# GPS_breakout-v10.net
KiCad netlist of a schematic drawn in EAGLE
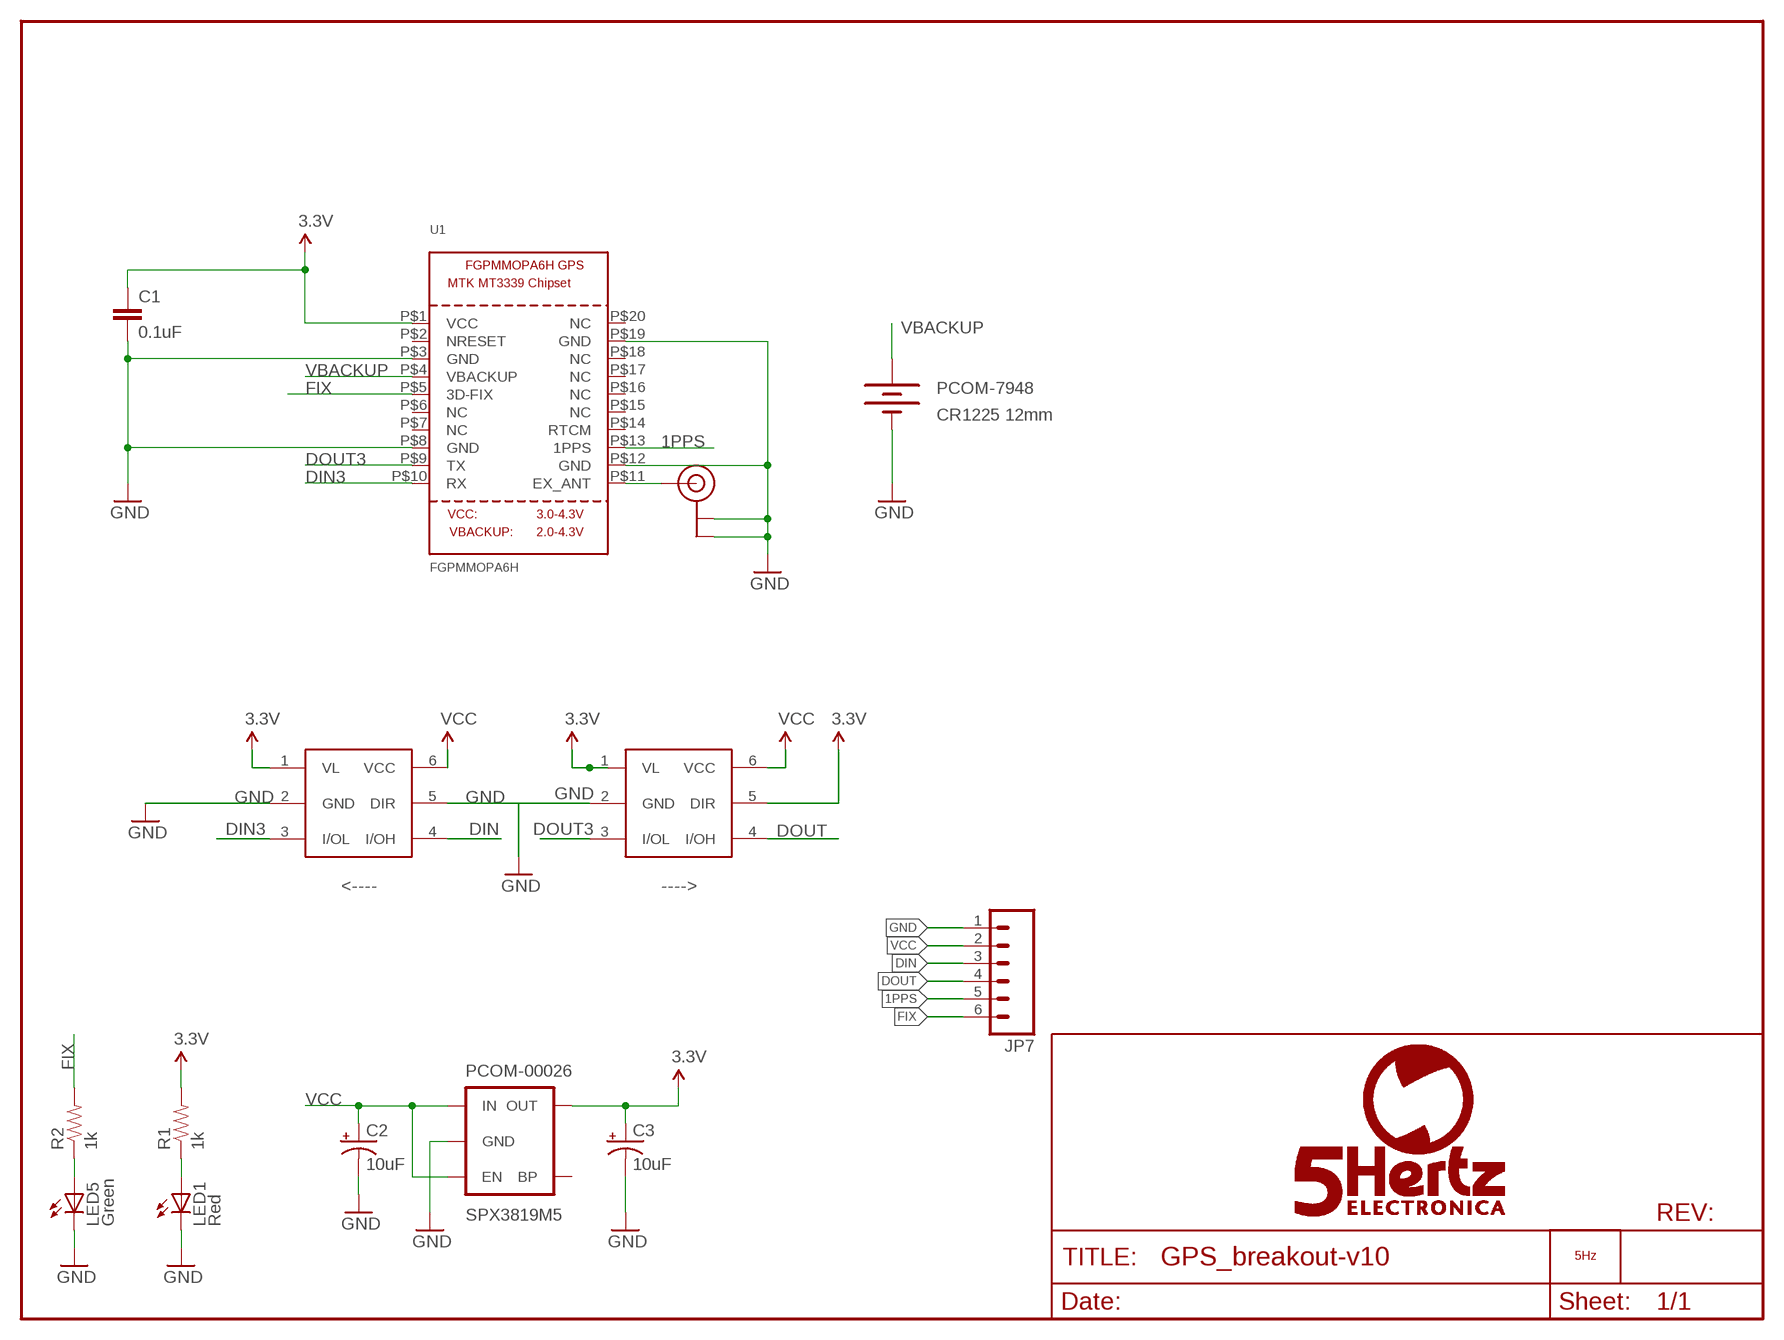
[diagram p0: schematic, sheet 1]

(export (version "E")
  (design (tool "Eeschema 10.0.6"))
  (components
    (comp (ref "C1")
      (value "0.1uF")
      (footprint "eagle-import:0603-CAP")
      (libsource (lib "eagle-import") (part "CAP0603-CAP"))
    )
    (comp (ref "C2")
      (value "10uF")
      (footprint "eagle-import:EIA3216")
      (libsource (lib "eagle-import") (part "CAP_POL1206"))
    )
    (comp (ref "C3")
      (value "10uF")
      (footprint "eagle-import:EIA3216")
      (libsource (lib "eagle-import") (part "CAP_POL1206"))
    )
    (comp (ref "JP7")
      (value "M06SIP")
      (footprint "eagle-import:1X06")
      (libsource (lib "eagle-import") (part "M06SIP"))
    )
    (comp (ref "LED1")
      (value "Red")
      (footprint "eagle-import:LED-0603")
      (libsource (lib "eagle-import") (part "LED0603"))
    )
    (comp (ref "LED5")
      (value "Green")
      (footprint "eagle-import:LED-0603")
      (libsource (lib "eagle-import") (part "LED0603"))
    )
    (comp (ref "LOGO1")
      (value "LOGO_5HZ_MAIN_15MM")
      (footprint "eagle-import:5HZ_LOGO_MAIN_15MM")
      (libsource (lib "eagle-import") (part "LOGO_5HZ_MAIN_15MM"))
    )
    (comp (ref "PCOM-00026")
      (value "SPX3819M5")
      (footprint "eagle-import:SOT23-5")
      (libsource (lib "eagle-import") (part "V_REG_LDOSMD"))
    )
    (comp (ref "PCOM-7948")
      (value "CR1225 12mm")
      (footprint "eagle-import:BATTCON_12MM_PTH")
      (libsource (lib "eagle-import") (part "BATTERY12PTH"))
    )
    (comp (ref "R1")
      (value "1k")
      (footprint "eagle-import:0603-RES")
      (libsource (lib "eagle-import") (part "RESISTOR0603-RES"))
    )
    (comp (ref "R2")
      (value "1k")
      (footprint "eagle-import:0603-RES")
      (libsource (lib "eagle-import") (part "RESISTOR0603-RES"))
    )
    (comp (ref "U$7")
      (value "MAX337")
      (footprint "eagle-import:SOT-363")
      (libsource (lib "eagle-import") (part "MAX337"))
    )
    (comp (ref "U$8")
      (value "MAX337")
      (footprint "eagle-import:SOT-363")
      (libsource (lib "eagle-import") (part "MAX337"))
    )
    (comp (ref "U$20")
      (value "U.FL")
      (footprint "eagle-import:U.FL")
      (libsource (lib "eagle-import") (part "U.FL"))
    )
    (comp (ref "U1")
      (value "FGPMMOPA6H")
      (footprint "eagle-import:FGPMMOPA6H")
      (libsource (lib "eagle-import") (part "GPS_FGPMMOPA6H"))
    )
  )
  (nets
    (net (code "1") (name "/DIN3") (class "Default")
      (node (ref "U$7") (pin "3") (pinfunction "I/OL_3") (pintype "bidirectional"))
      (node (ref "U1") (pin "P$10") (pinfunction "RX_P$10") (pintype "bidirectional"))
    )
    (net (code "2") (name "/DOUT3") (class "Default")
      (node (ref "U$8") (pin "3") (pinfunction "I/OL_3") (pintype "bidirectional"))
      (node (ref "U1") (pin "P$9") (pinfunction "TX_P$9") (pintype "bidirectional"))
    )
    (net (code "3") (name "/VBACKUP") (class "Default")
      (node (ref "PCOM-7948") (pin "VCC@1") (pinfunction "+_VCC@1") (pintype "power_in"))
      (node (ref "U1") (pin "P$4") (pinfunction "VBACKUP_P$4") (pintype "bidirectional"))
    )
    (net (code "4") (name "1PPS") (class "Default")
      (node (ref "JP7") (pin "5") (pinfunction "5_5") (pintype "passive"))
      (node (ref "U1") (pin "P$13") (pinfunction "1PPS_P$13") (pintype "bidirectional"))
    )
    (net (code "5") (name "3.3V") (class "Default")
      (node (ref "C1") (pin "1") (pinfunction "1_1") (pintype "passive"))
      (node (ref "C3") (pin "A") (pinfunction "+_A") (pintype "passive"))
      (node (ref "PCOM-00026") (pin "5") (pinfunction "OUT_5") (pintype "passive"))
      (node (ref "R1") (pin "2") (pinfunction "2_2") (pintype "passive"))
      (node (ref "U$7") (pin "1") (pinfunction "VL_1") (pintype "bidirectional"))
      (node (ref "U$8") (pin "1") (pinfunction "VL_1") (pintype "bidirectional"))
      (node (ref "U$8") (pin "5") (pinfunction "DIR_5") (pintype "bidirectional"))
      (node (ref "U1") (pin "P$1") (pinfunction "VCC_P$1") (pintype "bidirectional"))
    )
    (net (code "6") (name "DIN") (class "Default")
      (node (ref "JP7") (pin "3") (pinfunction "3_3") (pintype "passive"))
      (node (ref "U$7") (pin "4") (pinfunction "I/OH_4") (pintype "bidirectional"))
    )
    (net (code "7") (name "DOUT") (class "Default")
      (node (ref "JP7") (pin "4") (pinfunction "4_4") (pintype "passive"))
      (node (ref "U$8") (pin "4") (pinfunction "I/OH_4") (pintype "bidirectional"))
    )
    (net (code "8") (name "FIX") (class "Default")
      (node (ref "JP7") (pin "6") (pinfunction "6_6") (pintype "passive"))
      (node (ref "R2") (pin "2") (pinfunction "2_2") (pintype "passive"))
      (node (ref "U1") (pin "P$5") (pinfunction "3D-FIX_P$5") (pintype "bidirectional"))
    )
    (net (code "9") (name "GND") (class "Default")
      (node (ref "C1") (pin "2") (pinfunction "2_2") (pintype "passive"))
      (node (ref "C2") (pin "C") (pinfunction "-_C") (pintype "passive"))
      (node (ref "C3") (pin "C") (pinfunction "-_C") (pintype "passive"))
      (node (ref "JP7") (pin "1") (pinfunction "1_1") (pintype "passive"))
      (node (ref "LED1") (pin "C") (pinfunction "C_C") (pintype "passive"))
      (node (ref "LED5") (pin "C") (pinfunction "C_C") (pintype "passive"))
      (node (ref "PCOM-00026") (pin "2") (pinfunction "GND_2") (pintype "input"))
      (node (ref "PCOM-7948") (pin "GND") (pinfunction "-_GND") (pintype "power_in"))
      (node (ref "U$20") (pin "P$1") (pinfunction "GND_P$1") (pintype "bidirectional"))
      (node (ref "U$20") (pin "P$2") (pinfunction "GND_P$2") (pintype "bidirectional"))
      (node (ref "U$7") (pin "2") (pinfunction "GND_2") (pintype "bidirectional"))
      (node (ref "U$7") (pin "5") (pinfunction "DIR_5") (pintype "bidirectional"))
      (node (ref "U$8") (pin "2") (pinfunction "GND_2") (pintype "bidirectional"))
      (node (ref "U1") (pin "P$12") (pinfunction "GND_P$12") (pintype "bidirectional"))
      (node (ref "U1") (pin "P$19") (pinfunction "GND_P$19") (pintype "bidirectional"))
      (node (ref "U1") (pin "P$3") (pinfunction "GND_P$3") (pintype "bidirectional"))
      (node (ref "U1") (pin "P$8") (pinfunction "GND_P$8") (pintype "bidirectional"))
    )
    (net (code "10") (name "Net-(LED1-PadA)") (class "Default")
      (node (ref "LED1") (pin "A") (pinfunction "A_A") (pintype "passive"))
      (node (ref "R1") (pin "1") (pinfunction "1_1") (pintype "passive"))
    )
    (net (code "11") (name "Net-(LED5-PadA)") (class "Default")
      (node (ref "LED5") (pin "A") (pinfunction "A_A") (pintype "passive"))
      (node (ref "R2") (pin "1") (pinfunction "1_1") (pintype "passive"))
    )
    (net (code "12") (name "Net-(U$20-SIGNAL)") (class "Default")
      (node (ref "U$20") (pin "P$3") (pinfunction "SIGNAL_P$3") (pintype "bidirectional"))
      (node (ref "U1") (pin "P$11") (pinfunction "EX_ANT_P$11") (pintype "bidirectional"))
    )
    (net (code "13") (name "VCC") (class "Default")
      (node (ref "C2") (pin "A") (pinfunction "+_A") (pintype "passive"))
      (node (ref "JP7") (pin "2") (pinfunction "2_2") (pintype "passive"))
      (node (ref "PCOM-00026") (pin "1") (pinfunction "IN_1") (pintype "input"))
      (node (ref "PCOM-00026") (pin "3") (pinfunction "EN_3") (pintype "input"))
      (node (ref "U$7") (pin "6") (pinfunction "VCC_6") (pintype "bidirectional"))
      (node (ref "U$8") (pin "6") (pinfunction "VCC_6") (pintype "bidirectional"))
    )
    (net (code "14") (name "unconnected-(PCOM-00026-BP-Pad4)") (class "Default")
      (node (ref "PCOM-00026") (pin "4") (pinfunction "BP_4") (pintype "input"))
    )
    (net (code "15") (name "unconnected-(U1-NC-PadP$6)") (class "Default")
      (node (ref "U1") (pin "P$6") (pinfunction "NC_P$6") (pintype "bidirectional"))
    )
    (net (code "16") (name "unconnected-(U1-NC-PadP$7)") (class "Default")
      (node (ref "U1") (pin "P$7") (pinfunction "NC_P$7") (pintype "bidirectional"))
    )
    (net (code "17") (name "unconnected-(U1-NC-PadP$15)") (class "Default")
      (node (ref "U1") (pin "P$15") (pinfunction "NC_P$15") (pintype "bidirectional"))
    )
    (net (code "18") (name "unconnected-(U1-NC-PadP$16)") (class "Default")
      (node (ref "U1") (pin "P$16") (pinfunction "NC_P$16") (pintype "bidirectional"))
    )
    (net (code "19") (name "unconnected-(U1-NC-PadP$17)") (class "Default")
      (node (ref "U1") (pin "P$17") (pinfunction "NC_P$17") (pintype "bidirectional"))
    )
    (net (code "20") (name "unconnected-(U1-NC-PadP$18)") (class "Default")
      (node (ref "U1") (pin "P$18") (pinfunction "NC_P$18") (pintype "bidirectional"))
    )
    (net (code "21") (name "unconnected-(U1-NC-PadP$20)") (class "Default")
      (node (ref "U1") (pin "P$20") (pinfunction "NC_P$20") (pintype "bidirectional"))
    )
    (net (code "22") (name "unconnected-(U1-NRESET-PadP$2)") (class "Default")
      (node (ref "U1") (pin "P$2") (pinfunction "NRESET_P$2") (pintype "bidirectional"))
    )
    (net (code "23") (name "unconnected-(U1-RTCM-PadP$14)") (class "Default")
      (node (ref "U1") (pin "P$14") (pinfunction "RTCM_P$14") (pintype "bidirectional"))
    )
  )
)
